# Tray2_BCR_LT1513.net
KiCad netlist of a schematic drawn in Altium Designer
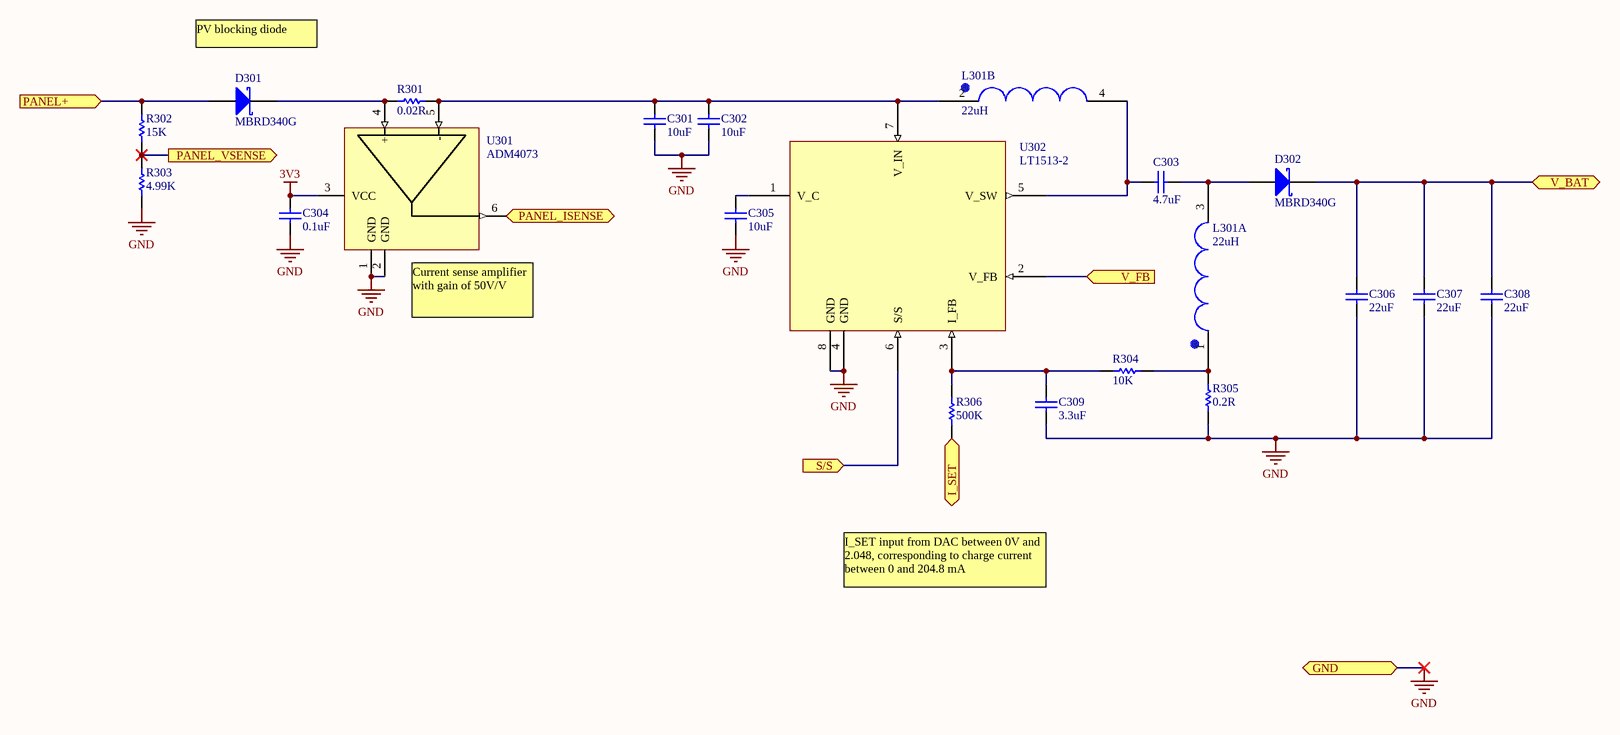
[diagram p0: Tray2_BCR_LT1513.SchDoc]

(export (version "E")
  (design (tool "Eeschema 10.0.6"))
  (components
    (comp (ref "C301")
      (value "10uF")
      (footprint "CAPC3225M")
      (description "Capacitor")
      (fields (field (name "Comment") "Cap") (field (name "PUBLISHER") "Altium Limited"))
      (libsource (lib "Miscellaneous Devices") (part "Cap"))
    )
    (comp (ref "C302")
      (value "10uF")
      (footprint "CAPC3225M")
      (description "Capacitor")
      (fields (field (name "Comment") "Cap") (field (name "PUBLISHER") "Altium Limited"))
      (libsource (lib "Miscellaneous Devices") (part "Cap"))
    )
    (comp (ref "C303")
      (value "4.7uF")
      (footprint "CAPC3225M")
      (description "Capacitor")
      (fields (field (name "Comment") "Cap") (field (name "PUBLISHER") "Altium Limited"))
      (libsource (lib "Miscellaneous Devices") (part "Cap"))
    )
    (comp (ref "C304")
      (value "0.1uF")
      (footprint "CAPC2012M")
      (description "Capacitor")
      (fields (field (name "Comment") "Cap") (field (name "PUBLISHER") "Altium Limited"))
      (libsource (lib "Miscellaneous Devices") (part "Cap"))
    )
    (comp (ref "C305")
      (value "10uF")
      (footprint "CAPC3216M")
      (description "Capacitor")
      (fields (field (name "Comment") "Cap") (field (name "PUBLISHER") "Altium Limited"))
      (libsource (lib "Miscellaneous Devices") (part "Cap"))
    )
    (comp (ref "C306")
      (value "22uF")
      (footprint "CAPC4532M")
      (description "Capacitor")
      (fields (field (name "Comment") "Cap") (field (name "PUBLISHER") "Altium Limited"))
      (libsource (lib "Miscellaneous Devices") (part "Cap"))
    )
    (comp (ref "C307")
      (value "22uF")
      (footprint "CAPC4532M")
      (description "Capacitor")
      (fields (field (name "Comment") "Cap") (field (name "PUBLISHER") "Altium Limited"))
      (libsource (lib "Miscellaneous Devices") (part "Cap"))
    )
    (comp (ref "C308")
      (value "22uF")
      (footprint "CAPC4532M")
      (description "Capacitor")
      (fields (field (name "Comment") "Cap") (field (name "PUBLISHER") "Altium Limited"))
      (libsource (lib "Miscellaneous Devices") (part "Cap"))
    )
    (comp (ref "C309")
      (value "3.3uF")
      (footprint "CAPC3216M")
      (description "Capacitor")
      (fields (field (name "Comment") "Cap") (field (name "PUBLISHER") "Altium Limited"))
      (libsource (lib "Miscellaneous Devices") (part "Cap"))
    )
    (comp (ref "D301")
      (value "MBRD340G")
      (footprint "TO229P990X238-3N")
      (description "Schottky Rectifier")
      (fields (field (name "PUBLISHER") "Altium Limited"))
      (libsource (lib "Miscellaneous Devices") (part "Diode 11DQ03"))
    )
    (comp (ref "D302")
      (value "MBRD340G")
      (footprint "TO229P990X238-3N")
      (description "Schottky Rectifier")
      (fields (field (name "PUBLISHER") "Altium Limited"))
      (libsource (lib "Miscellaneous Devices") (part "Diode 11DQ03"))
    )
    (comp (ref "L301")
      (value "22uH")
      (footprint "DRQ125")
      (fields (field (name "Comment") "DRQ125 Dual Inductor"))
      (libsource (lib "LT1513") (part "DRQ125 Dual Inductor"))
    )
    (comp (ref "R301")
      (value "0.02R")
      (footprint "RESC2012M")
      (description "Resistor")
      (fields (field (name "Comment") "Res1") (field (name "PUBLISHER") "Altium Limited"))
      (libsource (lib "Miscellaneous Devices") (part "Res1"))
    )
    (comp (ref "R302")
      (value "15K")
      (footprint "RESC2012M")
      (description "Resistor")
      (fields (field (name "Comment") "Res1") (field (name "PUBLISHER") "Altium Limited"))
      (libsource (lib "Miscellaneous Devices") (part "Res1"))
    )
    (comp (ref "R303")
      (value "4.99K")
      (footprint "RESC2012M")
      (description "Resistor")
      (fields (field (name "Comment") "Res1") (field (name "PUBLISHER") "Altium Limited"))
      (libsource (lib "Miscellaneous Devices") (part "Res1"))
    )
    (comp (ref "R304")
      (value "10K")
      (footprint "RESC2012M")
      (description "Resistor")
      (fields (field (name "Comment") "Res1") (field (name "PUBLISHER") "Altium Limited"))
      (libsource (lib "Miscellaneous Devices") (part "Res1"))
    )
    (comp (ref "R305")
      (value "0.2R")
      (footprint "RESC2012M")
      (description "Resistor")
      (fields (field (name "Comment") "Res1") (field (name "PUBLISHER") "Altium Limited"))
      (libsource (lib "Miscellaneous Devices") (part "Res1"))
    )
    (comp (ref "R306")
      (value "500K")
      (footprint "RESC2012M")
      (description "Resistor")
      (fields (field (name "Comment") "Res1") (field (name "PUBLISHER") "Altium Limited"))
      (libsource (lib "Miscellaneous Devices") (part "Res1"))
    )
    (comp (ref "U301")
      (value "ADM4073")
      (footprint "SOT26A-6N")
      (description "Current Sense Amplifer")
      (libsource (lib "Schlib1") (part "ADM4073"))
    )
    (comp (ref "U302")
      (value "LT1513-2")
      (footprint "LT1513-2_TO127P1420-8N")
      (libsource (lib "BCR") (part "LT1513-2"))
    )
  )
  (nets
    (net (code "1") (name "/I_SET") (class "Default")
      (node (ref "R306") (pin "2") (pinfunction "2_2") (pintype "passive"))
    )
    (net (code "2") (name "/PANEL+") (class "Default")
      (node (ref "D301") (pin "1") (pinfunction "A_1") (pintype "passive"))
      (node (ref "R302") (pin "2") (pinfunction "2_2") (pintype "passive"))
    )
    (net (code "3") (name "/PANEL_ISENSE") (class "Default") (node (ref "U301") (pin "6") (pintype "output")))
    (net (code "4") (name "/PANEL_VSENSE") (class "Default")
      (node (ref "R302") (pin "1") (pinfunction "1_1") (pintype "passive"))
      (node (ref "R303") (pin "2") (pinfunction "2_2") (pintype "passive"))
    )
    (net (code "5") (name "/S{slash}S") (class "Default")
      (node (ref "U302") (pin "6") (pinfunction "S/S_6") (pintype "input"))
    )
    (net (code "6") (name "/V_BAT") (class "Default")
      (node (ref "C306") (pin "1") (pinfunction "1_1") (pintype "passive"))
      (node (ref "C307") (pin "1") (pinfunction "1_1") (pintype "passive"))
      (node (ref "C308") (pin "1") (pinfunction "1_1") (pintype "passive"))
      (node (ref "D302") (pin "2") (pinfunction "K_2") (pintype "passive"))
    )
    (net (code "7") (name "/V_FB") (class "Default")
      (node (ref "U302") (pin "2") (pinfunction "V_FB_2") (pintype "input"))
    )
    (net (code "8") (name "3V3") (class "Default")
      (node (ref "C304") (pin "1") (pinfunction "1_1") (pintype "passive"))
      (node (ref "U301") (pin "3") (pinfunction "VCC_3") (pintype "passive"))
    )
    (net (code "9") (name "GND") (class "Default")
      (node (ref "C301") (pin "2") (pinfunction "2_2") (pintype "passive"))
      (node (ref "C302") (pin "2") (pinfunction "2_2") (pintype "passive"))
      (node (ref "C304") (pin "2") (pinfunction "2_2") (pintype "passive"))
      (node (ref "C305") (pin "2") (pinfunction "2_2") (pintype "passive"))
      (node (ref "C306") (pin "2") (pinfunction "2_2") (pintype "passive"))
      (node (ref "C307") (pin "2") (pinfunction "2_2") (pintype "passive"))
      (node (ref "C308") (pin "2") (pinfunction "2_2") (pintype "passive"))
      (node (ref "C309") (pin "1") (pinfunction "1_1") (pintype "passive"))
      (node (ref "R303") (pin "1") (pinfunction "1_1") (pintype "passive"))
      (node (ref "R305") (pin "1") (pinfunction "1_1") (pintype "passive"))
      (node (ref "U301") (pin "1") (pinfunction "GND_1") (pintype "passive"))
      (node (ref "U301") (pin "2") (pinfunction "GND_2") (pintype "passive"))
      (node (ref "U302") (pin "4") (pinfunction "GND_4") (pintype "passive"))
      (node (ref "U302") (pin "8") (pinfunction "GND_8") (pintype "passive"))
    )
    (net (code "10") (name "Net-(D301-K)") (class "Default")
      (node (ref "D301") (pin "2") (pinfunction "K_2") (pintype "passive"))
      (node (ref "R301") (pin "2") (pinfunction "2_2") (pintype "passive"))
      (node (ref "U301") (pin "4") (pinfunction "+_4") (pintype "input"))
    )
    (net (code "11") (name "Net-(D302-A)") (class "Default")
      (node (ref "C303") (pin "1") (pinfunction "1_1") (pintype "passive"))
      (node (ref "D302") (pin "1") (pinfunction "A_1") (pintype "passive"))
      (node (ref "L301") (pin "3") (pinfunction "18_3") (pintype "passive"))
    )
    (net (code "12") (name "Net-(L301A-17)") (class "Default")
      (node (ref "L301") (pin "1") (pinfunction "17_1") (pintype "passive"))
      (node (ref "R304") (pin "1") (pinfunction "1_1") (pintype "passive"))
      (node (ref "R305") (pin "2") (pinfunction "2_2") (pintype "passive"))
    )
    (net (code "13") (name "Net-(L301B-17)") (class "Default")
      (node (ref "C301") (pin "1") (pinfunction "1_1") (pintype "passive"))
      (node (ref "C302") (pin "1") (pinfunction "1_1") (pintype "passive"))
      (node (ref "L301") (pin "2") (pinfunction "17_2") (pintype "passive"))
      (node (ref "R301") (pin "1") (pinfunction "1_1") (pintype "passive"))
      (node (ref "U301") (pin "5") (pinfunction "-_5") (pintype "input"))
      (node (ref "U302") (pin "7") (pinfunction "V_IN_7") (pintype "input"))
    )
    (net (code "14") (name "Net-(L301B-18)") (class "Default")
      (node (ref "C303") (pin "2") (pinfunction "2_2") (pintype "passive"))
      (node (ref "L301") (pin "4") (pinfunction "18_4") (pintype "passive"))
      (node (ref "U302") (pin "5") (pinfunction "V_SW_5") (pintype "output"))
    )
    (net (code "15") (name "Net-(U302-I_FB)") (class "Default")
      (node (ref "C309") (pin "2") (pinfunction "2_2") (pintype "passive"))
      (node (ref "R304") (pin "2") (pinfunction "2_2") (pintype "passive"))
      (node (ref "R306") (pin "1") (pinfunction "1_1") (pintype "passive"))
      (node (ref "U302") (pin "3") (pinfunction "I_FB_3") (pintype "input"))
    )
    (net (code "16") (name "Net-(U302-V_C)") (class "Default")
      (node (ref "C305") (pin "1") (pinfunction "1_1") (pintype "passive"))
      (node (ref "U302") (pin "1") (pinfunction "V_C_1") (pintype "passive"))
    )
  )
)
